# x-IMU3-SA-Sync.net
KiCad netlist of a schematic drawn in Altium Designer
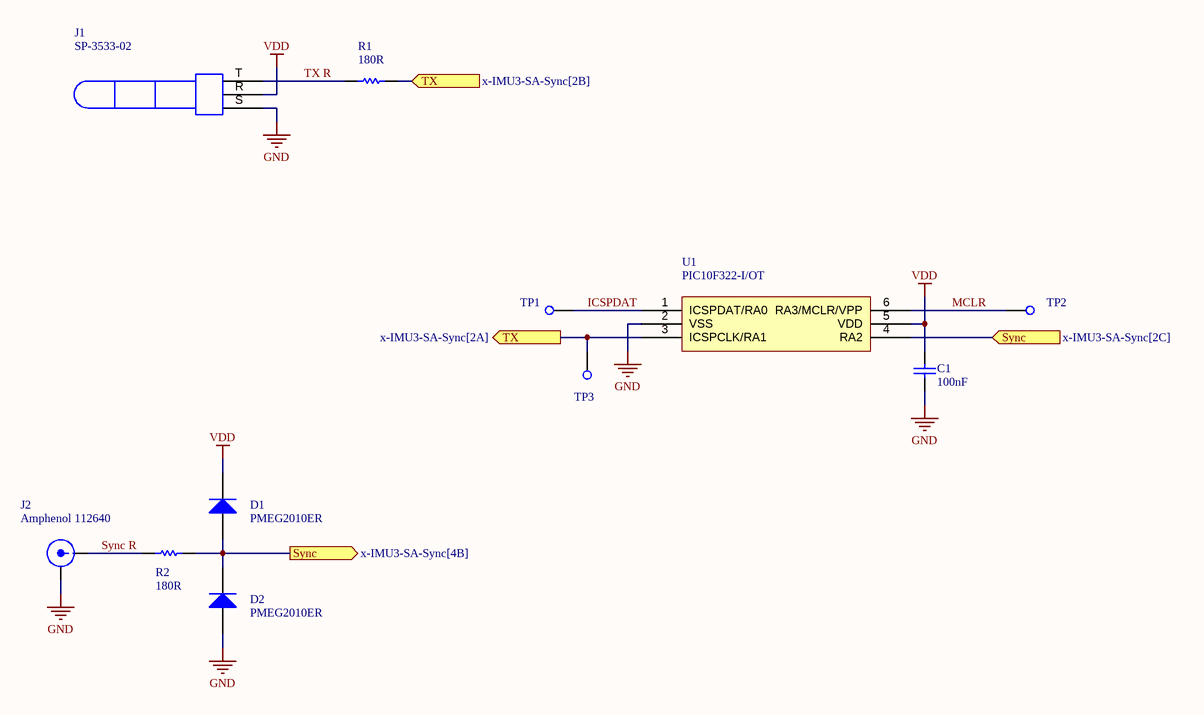
[diagram p0: x-IMU3-SA-Sync.SchDoc]

(export (version "E")
  (design (tool "Eeschema 10.0.6"))
  (components
    (comp (ref "C1") (value "100nF") (footprint "Capacitor 0402") (libsource (lib "x-io") (part "Capacitor")))
    (comp (ref "D1") (value "PMEG2010ER") (footprint "SOD-123") (libsource (lib "x-io") (part "Diode")))
    (comp (ref "D2") (value "PMEG2010ER") (footprint "SOD-123") (libsource (lib "x-io") (part "Diode")))
    (comp (ref "J1")
      (value "SP-3533-02")
      (footprint "SP-3533-02")
      (libsource (lib "x-io") (part "SP-3533-02"))
    )
    (comp (ref "J2")
      (value "Amphenol 112640")
      (footprint "Amphenol 112640")
      (libsource (lib "x-io") (part "BNC"))
    )
    (comp (ref "R1") (value "180R") (footprint "Resistor 0402") (libsource (lib "x-io") (part "Resistor")))
    (comp (ref "R2") (value "180R") (footprint "Resistor 0402") (libsource (lib "x-io") (part "Resistor")))
    (comp (ref "TP1")
      (value "Test Point")
      (footprint "Test Point 1mm")
      (libsource (lib "x-io") (part "Test Point"))
    )
    (comp (ref "TP2")
      (value "Test Point")
      (footprint "Test Point 1mm")
      (libsource (lib "x-io") (part "Test Point"))
    )
    (comp (ref "TP3")
      (value "Test Point")
      (footprint "Test Point 1mm")
      (libsource (lib "x-io") (part "Test Point"))
    )
    (comp (ref "U1")
      (value "PIC10F322-I/OT")
      (footprint "SOT-23-6")
      (libsource (lib "x-io") (part "PIC10F322-I/OT"))
    )
  )
  (nets
    (net (code "1") (name "/ICSPDAT") (class "Default")
      (node (ref "TP1") (pin "1") (pinfunction "1_1") (pintype "passive"))
      (node (ref "U1") (pin "1") (pinfunction "ICSPDAT/RA0_1") (pintype "passive"))
    )
    (net (code "2") (name "/MCLR") (class "Default")
      (node (ref "TP2") (pin "1") (pinfunction "1_1") (pintype "passive"))
      (node (ref "U1") (pin "6") (pinfunction "RA3/MCLR/VPP_6") (pintype "passive"))
    )
    (net (code "3") (name "/Sync") (class "Default")
      (node (ref "D1") (pin "A") (pinfunction "A_A") (pintype "passive"))
      (node (ref "D2") (pin "K") (pinfunction "K_K") (pintype "passive"))
      (node (ref "R2") (pin "2") (pinfunction "2_2") (pintype "passive"))
      (node (ref "U1") (pin "4") (pinfunction "RA2_4") (pintype "passive"))
    )
    (net (code "4") (name "/Sync R") (class "Default")
      (node (ref "J2") (pin "Signal") (pinfunction "Signal_Signal") (pintype "passive"))
      (node (ref "R2") (pin "1") (pinfunction "1_1") (pintype "passive"))
    )
    (net (code "5") (name "/TX") (class "Default")
      (node (ref "R1") (pin "2") (pinfunction "2_2") (pintype "passive"))
      (node (ref "TP3") (pin "1") (pinfunction "1_1") (pintype "passive"))
      (node (ref "U1") (pin "3") (pinfunction "ICSPCLK/RA1_3") (pintype "passive"))
    )
    (net (code "6") (name "/TX R") (class "Default")
      (node (ref "J1") (pin "T") (pinfunction "T_T") (pintype "passive"))
      (node (ref "R1") (pin "1") (pinfunction "1_1") (pintype "passive"))
    )
    (net (code "7") (name "GND") (class "Default")
      (node (ref "C1") (pin "1") (pinfunction "1_1") (pintype "passive"))
      (node (ref "D2") (pin "A") (pinfunction "A_A") (pintype "passive"))
      (node (ref "J1") (pin "S") (pinfunction "S_S") (pintype "passive"))
      (node (ref "J2") (pin "Shield") (pinfunction "Shield_Shield") (pintype "passive"))
      (node (ref "U1") (pin "2") (pinfunction "VSS_2") (pintype "passive"))
    )
    (net (code "8") (name "VDD") (class "Default")
      (node (ref "C1") (pin "2") (pinfunction "2_2") (pintype "passive"))
      (node (ref "D1") (pin "K") (pinfunction "K_K") (pintype "passive"))
      (node (ref "J1") (pin "R") (pinfunction "R_R") (pintype "passive"))
      (node (ref "U1") (pin "5") (pinfunction "VDD_5") (pintype "passive"))
    )
  )
)
